# untitled.net
KiCad netlist of a schematic drawn in EAGLE
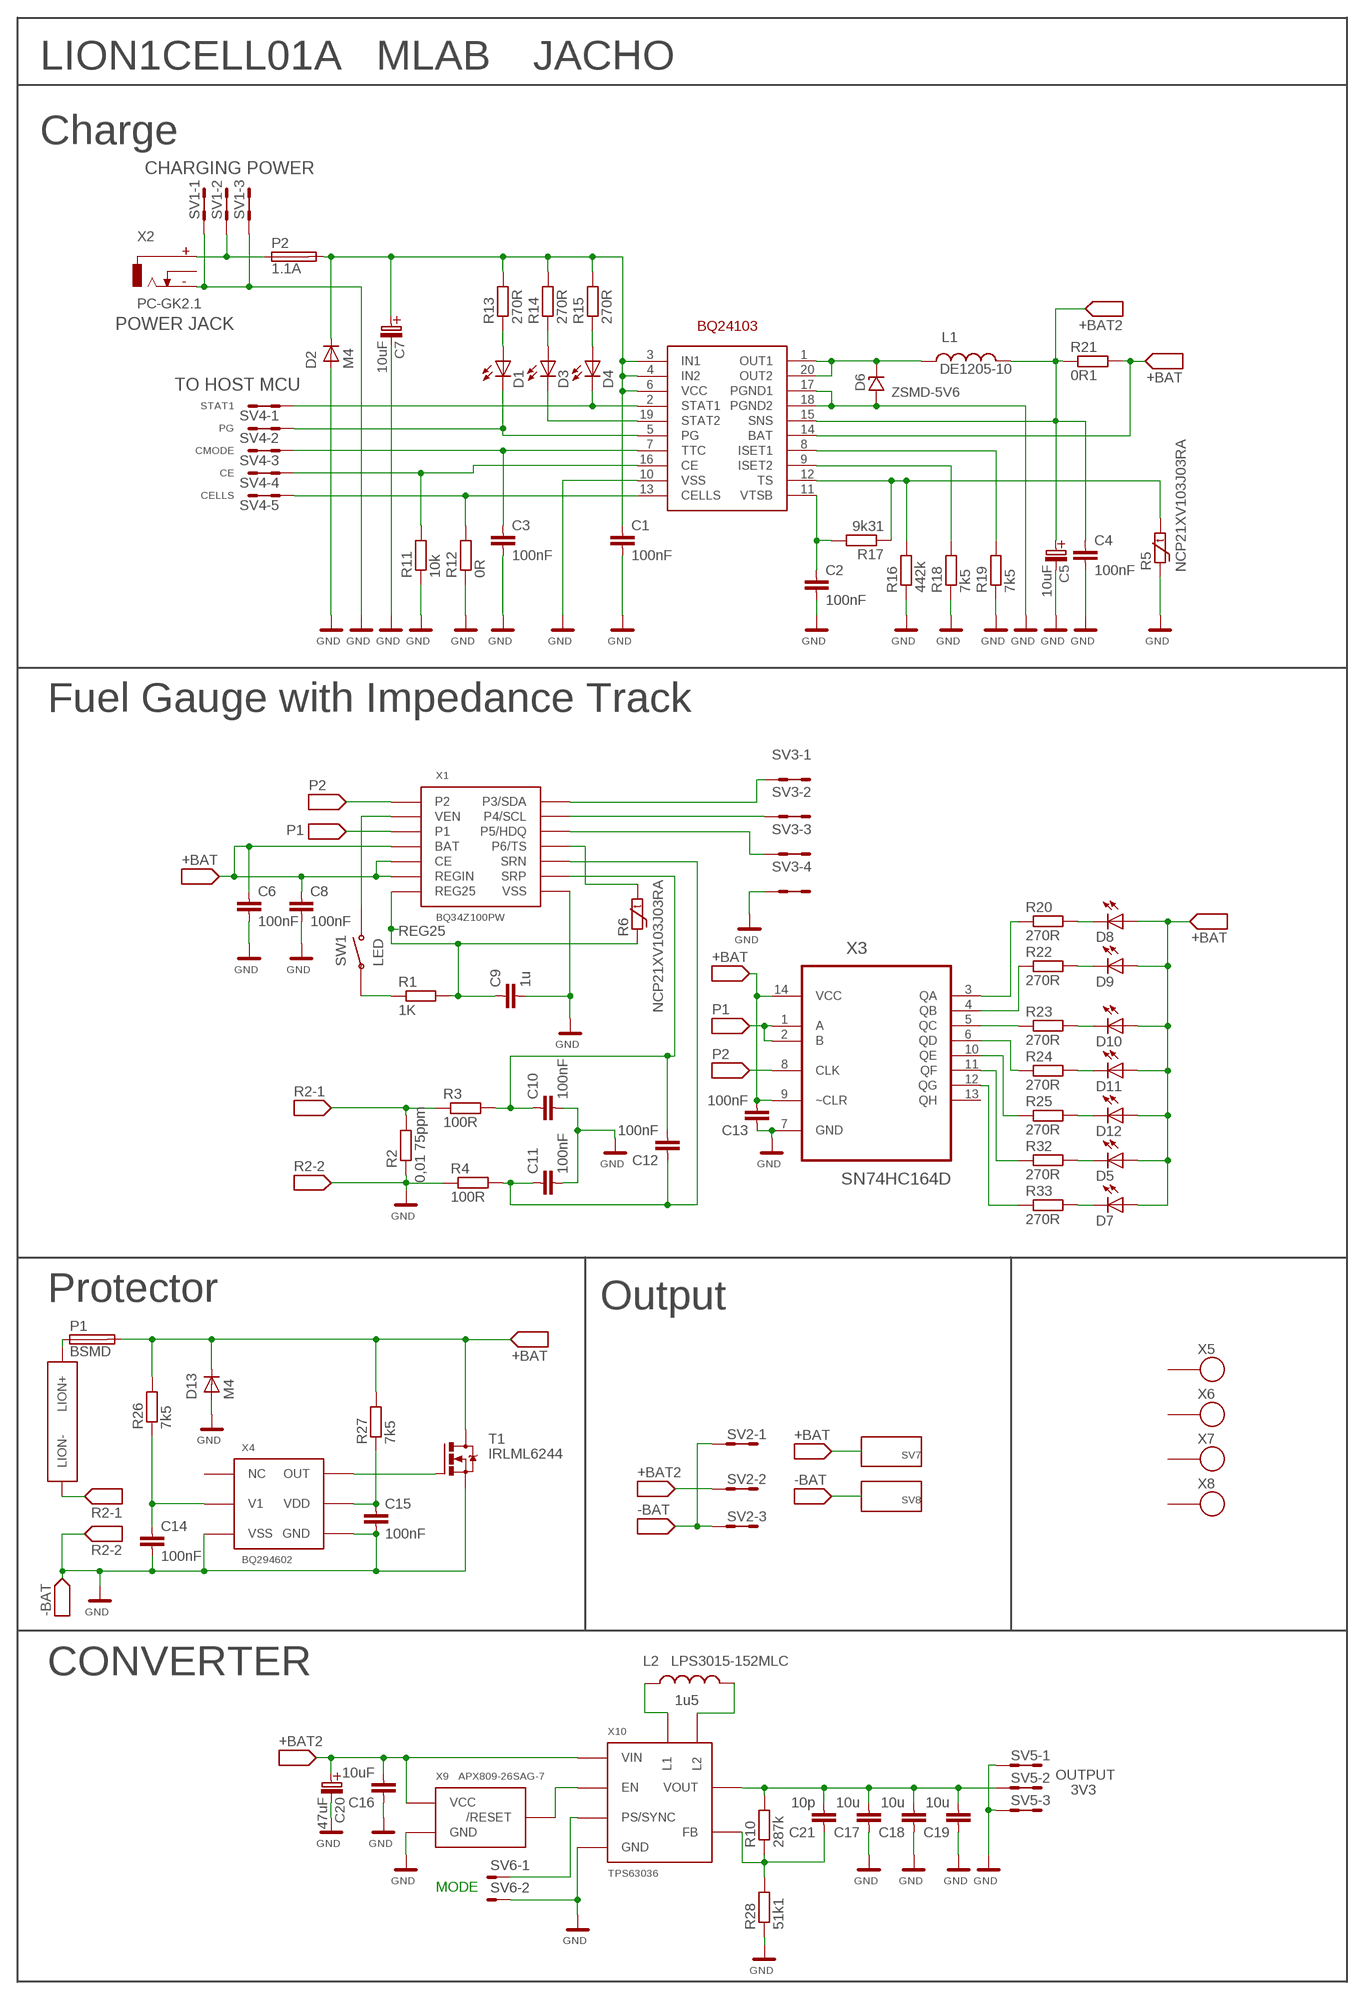
[diagram p0: schematic, sheet 1]

(export (version "E")
  (design (tool "Eeschema 10.0.6"))
  (components
    (comp (ref "C1")
      (value "100nF")
      (footprint "eagle-import:C0805")
      (libsource (lib "eagle-import") (part "C0805"))
    )
    (comp (ref "C2")
      (value "100nF")
      (footprint "eagle-import:C0805")
      (libsource (lib "eagle-import") (part "C0805"))
    )
    (comp (ref "C3")
      (value "100nF")
      (footprint "eagle-import:C0805")
      (libsource (lib "eagle-import") (part "C0805"))
    )
    (comp (ref "C4")
      (value "100nF")
      (footprint "eagle-import:C0805")
      (libsource (lib "eagle-import") (part "C0805"))
    )
    (comp (ref "C5") (value "10uF") (footprint "eagle-import:B") (libsource (lib "eagle-import") (part "B")))
    (comp (ref "C6")
      (value "100nF")
      (footprint "eagle-import:C0805")
      (libsource (lib "eagle-import") (part "C0805"))
    )
    (comp (ref "C7") (value "10uF") (footprint "eagle-import:B") (libsource (lib "eagle-import") (part "B")))
    (comp (ref "C8")
      (value "100nF")
      (footprint "eagle-import:C0805")
      (libsource (lib "eagle-import") (part "C0805"))
    )
    (comp (ref "C9")
      (value "1u")
      (footprint "eagle-import:C0805")
      (libsource (lib "eagle-import") (part "C0805"))
    )
    (comp (ref "C10")
      (value "100nF")
      (footprint "eagle-import:C0805")
      (libsource (lib "eagle-import") (part "C0805"))
    )
    (comp (ref "C11")
      (value "100nF")
      (footprint "eagle-import:C0805")
      (libsource (lib "eagle-import") (part "C0805"))
    )
    (comp (ref "C12")
      (value "100nF")
      (footprint "eagle-import:C0805")
      (libsource (lib "eagle-import") (part "C0805"))
    )
    (comp (ref "C13")
      (value "100nF")
      (footprint "eagle-import:C0805")
      (libsource (lib "eagle-import") (part "C0805"))
    )
    (comp (ref "C14")
      (value "100nF")
      (footprint "eagle-import:C0805")
      (libsource (lib "eagle-import") (part "C0805"))
    )
    (comp (ref "C15")
      (value "100nF")
      (footprint "eagle-import:C0805")
      (libsource (lib "eagle-import") (part "C0805"))
    )
    (comp (ref "C16")
      (value "10uF")
      (footprint "eagle-import:C0805")
      (libsource (lib "eagle-import") (part "C0805"))
    )
    (comp (ref "C17")
      (value "10u")
      (footprint "eagle-import:C0805")
      (libsource (lib "eagle-import") (part "C0805"))
    )
    (comp (ref "C18")
      (value "10u")
      (footprint "eagle-import:C0805")
      (libsource (lib "eagle-import") (part "C0805"))
    )
    (comp (ref "C19")
      (value "10u")
      (footprint "eagle-import:C0805")
      (libsource (lib "eagle-import") (part "C0805"))
    )
    (comp (ref "C20") (value "47uF") (footprint "eagle-import:B") (libsource (lib "eagle-import") (part "B")))
    (comp (ref "C21")
      (value "10p")
      (footprint "eagle-import:0603")
      (libsource (lib "eagle-import") (part "C0603"))
    )
    (comp (ref "D1")
      (value "LED1206_2")
      (footprint "eagle-import:1206_2")
      (libsource (lib "eagle-import") (part "LED1206_2"))
    )
    (comp (ref "D2")
      (value "M4")
      (footprint "eagle-import:SMB")
      (libsource (lib "eagle-import") (part "D-OB."))
    )
    (comp (ref "D3")
      (value "LED1206_2")
      (footprint "eagle-import:1206_2")
      (libsource (lib "eagle-import") (part "LED1206_2"))
    )
    (comp (ref "D4")
      (value "LED1206_2")
      (footprint "eagle-import:1206_2")
      (libsource (lib "eagle-import") (part "LED1206_2"))
    )
    (comp (ref "D5")
      (value "LED1206_2")
      (footprint "eagle-import:1206_2")
      (libsource (lib "eagle-import") (part "LED1206_2"))
    )
    (comp (ref "D6")
      (value "ZSMD-5V6")
      (footprint "eagle-import:MINIMELF")
      (libsource (lib "eagle-import") (part "D-ZENEROVA"))
    )
    (comp (ref "D7")
      (value "LED1206_2")
      (footprint "eagle-import:1206_2")
      (libsource (lib "eagle-import") (part "LED1206_2"))
    )
    (comp (ref "D8")
      (value "LED1206_2")
      (footprint "eagle-import:1206_2")
      (libsource (lib "eagle-import") (part "LED1206_2"))
    )
    (comp (ref "D9")
      (value "LED1206_2")
      (footprint "eagle-import:1206_2")
      (libsource (lib "eagle-import") (part "LED1206_2"))
    )
    (comp (ref "D10")
      (value "LED1206_2")
      (footprint "eagle-import:1206_2")
      (libsource (lib "eagle-import") (part "LED1206_2"))
    )
    (comp (ref "D11")
      (value "LED1206_2")
      (footprint "eagle-import:1206_2")
      (libsource (lib "eagle-import") (part "LED1206_2"))
    )
    (comp (ref "D12")
      (value "LED1206_2")
      (footprint "eagle-import:1206_2")
      (libsource (lib "eagle-import") (part "LED1206_2"))
    )
    (comp (ref "D13")
      (value "M4")
      (footprint "eagle-import:SMA")
      (libsource (lib "eagle-import") (part "D-OB.SMA"))
    )
    (comp (ref "L1")
      (value "DE1205-10")
      (footprint "eagle-import:DE1205-10")
      (libsource (lib "eagle-import") (part "DE1205-10"))
    )
    (comp (ref "L2")
      (value "LPS3015-152MLC")
      (footprint "eagle-import:LPS3015")
      (libsource (lib "eagle-import") (part "LPS3015"))
    )
    (comp (ref "P1")
      (value "BSMD")
      (footprint "eagle-import:2410")
      (libsource (lib "eagle-import") (part "POJISTKA2410"))
    )
    (comp (ref "P2")
      (value "1.1A")
      (footprint "eagle-import:1812")
      (libsource (lib "eagle-import") (part "POJISTKA_1812"))
    )
    (comp (ref "R1")
      (value "1K")
      (footprint "eagle-import:0805")
      (libsource (lib "eagle-import") (part "R0805"))
    )
    (comp (ref "R2")
      (value "0,01 75ppm")
      (footprint "eagle-import:0805")
      (libsource (lib "eagle-import") (part "R0805"))
    )
    (comp (ref "R3")
      (value "100R")
      (footprint "eagle-import:0805")
      (libsource (lib "eagle-import") (part "R0805"))
    )
    (comp (ref "R4")
      (value "100R")
      (footprint "eagle-import:0805")
      (libsource (lib "eagle-import") (part "R0805"))
    )
    (comp (ref "R5")
      (value "NCP21XV103J03RA")
      (footprint "eagle-import:0805")
      (libsource (lib "eagle-import") (part "TERMISTOR0805"))
    )
    (comp (ref "R6")
      (value "NCP21XV103J03RA")
      (footprint "eagle-import:0805")
      (libsource (lib "eagle-import") (part "TERMISTOR0805"))
    )
    (comp (ref "R10")
      (value "287k")
      (footprint "eagle-import:0603")
      (libsource (lib "eagle-import") (part "R0603"))
    )
    (comp (ref "R11")
      (value "10k")
      (footprint "eagle-import:0805")
      (libsource (lib "eagle-import") (part "R0805"))
    )
    (comp (ref "R12")
      (value "0R")
      (footprint "eagle-import:0805")
      (libsource (lib "eagle-import") (part "R0805"))
    )
    (comp (ref "R13")
      (value "270R")
      (footprint "eagle-import:0805")
      (libsource (lib "eagle-import") (part "R0805"))
    )
    (comp (ref "R14")
      (value "270R")
      (footprint "eagle-import:0805")
      (libsource (lib "eagle-import") (part "R0805"))
    )
    (comp (ref "R15")
      (value "270R")
      (footprint "eagle-import:0805")
      (libsource (lib "eagle-import") (part "R0805"))
    )
    (comp (ref "R16")
      (value "442k")
      (footprint "eagle-import:0805")
      (libsource (lib "eagle-import") (part "R0805"))
    )
    (comp (ref "R17")
      (value "9k31")
      (footprint "eagle-import:0805")
      (libsource (lib "eagle-import") (part "R0805"))
    )
    (comp (ref "R18")
      (value "7k5")
      (footprint "eagle-import:0805")
      (libsource (lib "eagle-import") (part "R0805"))
    )
    (comp (ref "R19")
      (value "7k5")
      (footprint "eagle-import:0805")
      (libsource (lib "eagle-import") (part "R0805"))
    )
    (comp (ref "R20")
      (value "270R")
      (footprint "eagle-import:0805")
      (libsource (lib "eagle-import") (part "R0805"))
    )
    (comp (ref "R21")
      (value "0R1")
      (footprint "eagle-import:R2512")
      (libsource (lib "eagle-import") (part "R-EU_R2512"))
    )
    (comp (ref "R22")
      (value "270R")
      (footprint "eagle-import:0805")
      (libsource (lib "eagle-import") (part "R0805"))
    )
    (comp (ref "R23")
      (value "270R")
      (footprint "eagle-import:0805")
      (libsource (lib "eagle-import") (part "R0805"))
    )
    (comp (ref "R24")
      (value "270R")
      (footprint "eagle-import:0805")
      (libsource (lib "eagle-import") (part "R0805"))
    )
    (comp (ref "R25")
      (value "270R")
      (footprint "eagle-import:0805")
      (libsource (lib "eagle-import") (part "R0805"))
    )
    (comp (ref "R26")
      (value "7k5")
      (footprint "eagle-import:0805")
      (libsource (lib "eagle-import") (part "R0805"))
    )
    (comp (ref "R27")
      (value "7k5")
      (footprint "eagle-import:0805")
      (libsource (lib "eagle-import") (part "R0805"))
    )
    (comp (ref "R28")
      (value "51k1")
      (footprint "eagle-import:0603")
      (libsource (lib "eagle-import") (part "R0603"))
    )
    (comp (ref "R32")
      (value "270R")
      (footprint "eagle-import:0805")
      (libsource (lib "eagle-import") (part "R0805"))
    )
    (comp (ref "R33")
      (value "270R")
      (footprint "eagle-import:0805")
      (libsource (lib "eagle-import") (part "R0805"))
    )
    (comp (ref "SV1")
      (value "MA03-2")
      (footprint "eagle-import:MA03-2")
      (libsource (lib "eagle-import") (part "MA03-2"))
    )
    (comp (ref "SV2")
      (value "MA03-2")
      (footprint "eagle-import:MA03-2")
      (libsource (lib "eagle-import") (part "MA03-2"))
    )
    (comp (ref "SV3")
      (value "MA04-2")
      (footprint "eagle-import:MA04-2")
      (libsource (lib "eagle-import") (part "MA04-2"))
    )
    (comp (ref "SV4")
      (value "MA05-2")
      (footprint "eagle-import:MA05-2")
      (libsource (lib "eagle-import") (part "MA05-2"))
    )
    (comp (ref "SV5")
      (value "MA03-2")
      (footprint "eagle-import:MA03-2")
      (libsource (lib "eagle-import") (part "MA03-2"))
    )
    (comp (ref "SV6")
      (value "MA02-1")
      (footprint "eagle-import:MA02-1")
      (libsource (lib "eagle-import") (part "MA02-1"))
    )
    (comp (ref "SV7")
      (value "WAGO256")
      (footprint "eagle-import:WAGO256")
      (libsource (lib "eagle-import") (part "WAGO256"))
    )
    (comp (ref "SV8")
      (value "WAGO256")
      (footprint "eagle-import:WAGO256")
      (libsource (lib "eagle-import") (part "WAGO256"))
    )
    (comp (ref "SW1")
      (value "TACT-64K")
      (footprint "eagle-import:TACT-64K")
      (libsource (lib "eagle-import") (part "TACT-64K"))
    )
    (comp (ref "T1")
      (value "IRLML6244")
      (footprint "eagle-import:SOT23")
      (libsource (lib "eagle-import") (part "IRLML6244TRPBF"))
    )
    (comp (ref "U$2")
      (value "LION1")
      (footprint "eagle-import:LION1")
      (libsource (lib "eagle-import") (part "LION1"))
    )
    (comp (ref "U1")
      (value "BQ24103")
      (footprint "eagle-import:RHL_R-VQFN-N20")
      (libsource (lib "eagle-import") (part "BQ24103"))
    )
    (comp (ref "X1")
      (value "BQ34Z100PW")
      (footprint "eagle-import:TSSOP14")
      (libsource (lib "eagle-import") (part "BQ34Z100PW"))
    )
    (comp (ref "X2")
      (value "DC2.1MM")
      (footprint "eagle-import:DC2.1MM")
      (libsource (lib "eagle-import") (part "DC2.1MM"))
    )
    (comp (ref "X3")
      (value "SN74HC164D")
      (footprint "eagle-import:SOIC127P600X175-14N")
      (libsource (lib "eagle-import") (part "SN74HC164D"))
    )
    (comp (ref "X4")
      (value "BQ294602")
      (footprint "eagle-import:SON_N6")
      (libsource (lib "eagle-import") (part "BQ294602"))
    )
    (comp (ref "X5")
      (value "SROUB3M")
      (footprint "eagle-import:SROUB3M")
      (libsource (lib "eagle-import") (part "SROUB3M"))
    )
    (comp (ref "X6")
      (value "SROUB3M")
      (footprint "eagle-import:SROUB3M")
      (libsource (lib "eagle-import") (part "SROUB3M"))
    )
    (comp (ref "X7")
      (value "SROUB3M")
      (footprint "eagle-import:SROUB3M")
      (libsource (lib "eagle-import") (part "SROUB3M"))
    )
    (comp (ref "X8")
      (value "SROUB3M")
      (footprint "eagle-import:SROUB3M")
      (libsource (lib "eagle-import") (part "SROUB3M"))
    )
    (comp (ref "X9")
      (value "APX809-26SAG-7")
      (footprint "eagle-import:SOT23")
      (libsource (lib "eagle-import") (part "APX809-26SA"))
    )
    (comp (ref "X10")
      (value "TPS63036")
      (footprint "eagle-import:DSBGA8")
      (libsource (lib "eagle-import") (part "TPS63036"))
    )
  )
  (nets
    (net (code "1") (name "/+BAT") (class "Default")
      (node (ref "C13") (pin "2") (pinfunction "2_2") (pintype "passive"))
      (node (ref "C6") (pin "1") (pinfunction "1_1") (pintype "passive"))
      (node (ref "C8") (pin "1") (pinfunction "1_1") (pintype "passive"))
      (node (ref "D10") (pin "A") (pinfunction "A_A") (pintype "passive"))
      (node (ref "D11") (pin "A") (pinfunction "A_A") (pintype "passive"))
      (node (ref "D12") (pin "A") (pinfunction "A_A") (pintype "passive"))
      (node (ref "D13") (pin "K") (pinfunction "C_K") (pintype "passive"))
      (node (ref "D5") (pin "A") (pinfunction "A_A") (pintype "passive"))
      (node (ref "D7") (pin "A") (pinfunction "A_A") (pintype "passive"))
      (node (ref "D8") (pin "A") (pinfunction "A_A") (pintype "passive"))
      (node (ref "D9") (pin "A") (pinfunction "A_A") (pintype "passive"))
      (node (ref "P1") (pin "2") (pinfunction "2_2") (pintype "passive"))
      (node (ref "R21") (pin "2") (pinfunction "2_2") (pintype "passive"))
      (node (ref "R26") (pin "2") (pinfunction "2_2") (pintype "passive"))
      (node (ref "R27") (pin "2") (pinfunction "2_2") (pintype "passive"))
      (node (ref "SV7") (pin "1") (pinfunction "P$1_1") (pintype "passive"))
      (node (ref "SV7") (pin "A1") (pinfunction "P$1_A1") (pintype "passive"))
      (node (ref "T1") (pin "3") (pinfunction "D_3") (pintype "passive"))
      (node (ref "U1") (pin "14") (pinfunction "BAT_14") (pintype "bidirectional"))
      (node (ref "X1") (pin "4") (pinfunction "BAT_4") (pintype "bidirectional"))
      (node (ref "X1") (pin "5") (pinfunction "CE_5") (pintype "bidirectional"))
      (node (ref "X1") (pin "6") (pinfunction "REGIN_6") (pintype "bidirectional"))
      (node (ref "X3") (pin "14") (pinfunction "VCC_14") (pintype "power_in"))
      (node (ref "X3") (pin "9") (pinfunction "~{CLR}_9") (pintype "input"))
    )
    (net (code "2") (name "/+BAT2") (class "Default")
      (node (ref "C16") (pin "2") (pinfunction "2_2") (pintype "passive"))
      (node (ref "C20") (pin "+") (pinfunction "C_EL+_+") (pintype "passive"))
      (node (ref "C4") (pin "1") (pinfunction "1_1") (pintype "passive"))
      (node (ref "C5") (pin "+") (pinfunction "C_EL+_+") (pintype "passive"))
      (node (ref "L1") (pin "P$2") (pinfunction "2_P$2") (pintype "passive"))
      (node (ref "R21") (pin "1") (pinfunction "1_1") (pintype "passive"))
      (node (ref "SV2") (pin "3") (pinfunction "K_3") (pintype "passive"))
      (node (ref "SV2") (pin "4") (pinfunction "K_4") (pintype "passive"))
      (node (ref "U1") (pin "15") (pinfunction "SNS_15") (pintype "bidirectional"))
      (node (ref "X10") (pin "A1") (pinfunction "VIN_A1") (pintype "input"))
      (node (ref "X9") (pin "3") (pinfunction "VCC_3") (pintype "input"))
    )
    (net (code "3") (name "/P1") (class "Default")
      (node (ref "X1") (pin "3") (pinfunction "P1_3") (pintype "bidirectional"))
      (node (ref "X3") (pin "1") (pinfunction "A_1") (pintype "input"))
      (node (ref "X3") (pin "2") (pinfunction "B_2") (pintype "input"))
    )
    (net (code "4") (name "/P2") (class "Default")
      (node (ref "X1") (pin "1") (pinfunction "P2_1") (pintype "bidirectional"))
      (node (ref "X3") (pin "8") (pinfunction "CLK_8") (pintype "input"))
    )
    (net (code "5") (name "/R2") (class "Default")
      (node (ref "R2") (pin "2") (pinfunction "2_2") (pintype "passive"))
      (node (ref "R3") (pin "1") (pinfunction "1_1") (pintype "passive"))
      (node (ref "U$2") (pin "-") (pinfunction "LION-_-") (pintype "bidirectional"))
      (node (ref "U$2") (pin "-1") (pinfunction "LION-_-1") (pintype "bidirectional"))
    )
    (net (code "6") (name "GND") (class "Default")
      (node (ref "C1") (pin "2") (pinfunction "2_2") (pintype "passive"))
      (node (ref "C10") (pin "2") (pinfunction "2_2") (pintype "passive"))
      (node (ref "C11") (pin "2") (pinfunction "2_2") (pintype "passive"))
      (node (ref "C13") (pin "1") (pinfunction "1_1") (pintype "passive"))
      (node (ref "C14") (pin "2") (pinfunction "2_2") (pintype "passive"))
      (node (ref "C15") (pin "2") (pinfunction "2_2") (pintype "passive"))
      (node (ref "C16") (pin "1") (pinfunction "1_1") (pintype "passive"))
      (node (ref "C17") (pin "1") (pinfunction "1_1") (pintype "passive"))
      (node (ref "C18") (pin "1") (pinfunction "1_1") (pintype "passive"))
      (node (ref "C19") (pin "1") (pinfunction "1_1") (pintype "passive"))
      (node (ref "C2") (pin "2") (pinfunction "2_2") (pintype "passive"))
      (node (ref "C20") (pin "-") (pinfunction "C_EL-_-") (pintype "passive"))
      (node (ref "C3") (pin "2") (pinfunction "2_2") (pintype "passive"))
      (node (ref "C4") (pin "2") (pinfunction "2_2") (pintype "passive"))
      (node (ref "C5") (pin "-") (pinfunction "C_EL-_-") (pintype "passive"))
      (node (ref "C6") (pin "2") (pinfunction "2_2") (pintype "passive"))
      (node (ref "C7") (pin "-") (pinfunction "C_EL-_-") (pintype "passive"))
      (node (ref "C8") (pin "2") (pinfunction "2_2") (pintype "passive"))
      (node (ref "C9") (pin "2") (pinfunction "2_2") (pintype "passive"))
      (node (ref "D13") (pin "A") (pinfunction "A_A") (pintype "passive"))
      (node (ref "D2") (pin "A") (pinfunction "A_A") (pintype "passive"))
      (node (ref "D6") (pin "A") (pinfunction "A_A") (pintype "passive"))
      (node (ref "R11") (pin "1") (pinfunction "1_1") (pintype "passive"))
      (node (ref "R12") (pin "1") (pinfunction "1_1") (pintype "passive"))
      (node (ref "R16") (pin "1") (pinfunction "1_1") (pintype "passive"))
      (node (ref "R18") (pin "1") (pinfunction "1_1") (pintype "passive"))
      (node (ref "R19") (pin "1") (pinfunction "1_1") (pintype "passive"))
      (node (ref "R2") (pin "1") (pinfunction "1_1") (pintype "passive"))
      (node (ref "R28") (pin "1") (pinfunction "1_1") (pintype "passive"))
      (node (ref "R4") (pin "1") (pinfunction "1_1") (pintype "passive"))
      (node (ref "R5") (pin "1") (pinfunction "1_1") (pintype "passive"))
      (node (ref "SV1") (pin "1") (pinfunction "K_1") (pintype "passive"))
      (node (ref "SV1") (pin "2") (pinfunction "K_2") (pintype "passive"))
      (node (ref "SV1") (pin "5") (pinfunction "K_5") (pintype "passive"))
      (node (ref "SV1") (pin "6") (pinfunction "K_6") (pintype "passive"))
      (node (ref "SV2") (pin "1") (pinfunction "K_1") (pintype "passive"))
      (node (ref "SV2") (pin "2") (pinfunction "K_2") (pintype "passive"))
      (node (ref "SV2") (pin "5") (pinfunction "K_5") (pintype "passive"))
      (node (ref "SV2") (pin "6") (pinfunction "K_6") (pintype "passive"))
      (node (ref "SV3") (pin "7") (pinfunction "K_7") (pintype "passive"))
      (node (ref "SV3") (pin "8") (pinfunction "K_8") (pintype "passive"))
      (node (ref "SV5") (pin "1") (pinfunction "K_1") (pintype "passive"))
      (node (ref "SV5") (pin "2") (pinfunction "K_2") (pintype "passive"))
      (node (ref "SV5") (pin "5") (pinfunction "K_5") (pintype "passive"))
      (node (ref "SV5") (pin "6") (pinfunction "K_6") (pintype "passive"))
      (node (ref "SV6") (pin "2") (pinfunction "P$1_2") (pintype "passive"))
      (node (ref "SV8") (pin "1") (pinfunction "P$1_1") (pintype "passive"))
      (node (ref "SV8") (pin "A1") (pinfunction "P$1_A1") (pintype "passive"))
      (node (ref "T1") (pin "2") (pinfunction "S_2") (pintype "passive"))
      (node (ref "U1") (pin "10") (pinfunction "VSS_10") (pintype "bidirectional"))
      (node (ref "U1") (pin "17") (pinfunction "PGND1_17") (pintype "bidirectional"))
      (node (ref "U1") (pin "18") (pinfunction "PGND2_18") (pintype "bidirectional"))
      (node (ref "X1") (pin "8") (pinfunction "VSS_8") (pintype "bidirectional"))
      (node (ref "X10") (pin "C2") (pinfunction "GND_C2") (pintype "passive"))
      (node (ref "X2") (pin "GND") (pinfunction "-_GND") (pintype "passive"))
      (node (ref "X3") (pin "7") (pinfunction "GND_7") (pintype "passive"))
      (node (ref "X4") (pin "3") (pinfunction "VSS_3") (pintype "bidirectional"))
      (node (ref "X4") (pin "4") (pinfunction "VSS_4") (pintype "bidirectional"))
      (node (ref "X4") (pin "7") (pinfunction "GND_7") (pintype "bidirectional"))
      (node (ref "X9") (pin "1") (pinfunction "GND_1") (pintype "passive"))
    )
    (net (code "7") (name "Net-(C7-C_EL+)") (class "Default")
      (node (ref "C1") (pin "1") (pinfunction "1_1") (pintype "passive"))
      (node (ref "C7") (pin "+") (pinfunction "C_EL+_+") (pintype "passive"))
      (node (ref "D2") (pin "K") (pinfunction "C_K") (pintype "passive"))
      (node (ref "P2") (pin "2") (pinfunction "2_2") (pintype "passive"))
      (node (ref "R13") (pin "2") (pinfunction "2_2") (pintype "passive"))
      (node (ref "R14") (pin "2") (pinfunction "2_2") (pintype "passive"))
      (node (ref "R15") (pin "2") (pinfunction "2_2") (pintype "passive"))
      (node (ref "U1") (pin "3") (pinfunction "IN1_3") (pintype "bidirectional"))
      (node (ref "U1") (pin "4") (pinfunction "IN2_4") (pintype "bidirectional"))
      (node (ref "U1") (pin "6") (pinfunction "VCC_6") (pintype "bidirectional"))
    )
    (net (code "8") (name "Net-(D1-C)") (class "Default")
      (node (ref "D1") (pin "K") (pinfunction "C_K") (pintype "passive"))
      (node (ref "SV4") (pin "3") (pinfunction "K_3") (pintype "passive"))
      (node (ref "SV4") (pin "4") (pinfunction "K_4") (pintype "passive"))
      (node (ref "U1") (pin "5") (pinfunction "PG_5") (pintype "bidirectional"))
    )
    (net (code "9") (name "Net-(D1-PadA)") (class "Default")
      (node (ref "D1") (pin "A") (pinfunction "A_A") (pintype "passive"))
      (node (ref "R13") (pin "1") (pinfunction "1_1") (pintype "passive"))
    )
    (net (code "10") (name "Net-(D3-C)") (class "Default")
      (node (ref "D3") (pin "K") (pinfunction "C_K") (pintype "passive"))
      (node (ref "U1") (pin "19") (pinfunction "STAT2_19") (pintype "bidirectional"))
    )
    (net (code "11") (name "Net-(D3-PadA)") (class "Default")
      (node (ref "D3") (pin "A") (pinfunction "A_A") (pintype "passive"))
      (node (ref "R14") (pin "1") (pinfunction "1_1") (pintype "passive"))
    )
    (net (code "12") (name "Net-(D4-C)") (class "Default")
      (node (ref "D4") (pin "K") (pinfunction "C_K") (pintype "passive"))
      (node (ref "SV4") (pin "1") (pinfunction "K_1") (pintype "passive"))
      (node (ref "SV4") (pin "2") (pinfunction "K_2") (pintype "passive"))
      (node (ref "U1") (pin "2") (pinfunction "STAT1_2") (pintype "bidirectional"))
    )
    (net (code "13") (name "Net-(D4-PadA)") (class "Default")
      (node (ref "D4") (pin "A") (pinfunction "A_A") (pintype "passive"))
      (node (ref "R15") (pin "1") (pinfunction "1_1") (pintype "passive"))
    )
    (net (code "14") (name "Net-(D5-C)") (class "Default")
      (node (ref "D5") (pin "K") (pinfunction "C_K") (pintype "passive"))
      (node (ref "R32") (pin "2") (pinfunction "2_2") (pintype "passive"))
    )
    (net (code "15") (name "Net-(D6-K)") (class "Default")
      (node (ref "D6") (pin "C") (pinfunction "K_C") (pintype "passive"))
      (node (ref "L1") (pin "P$1") (pinfunction "1_P$1") (pintype "passive"))
      (node (ref "U1") (pin "1") (pinfunction "OUT1_1") (pintype "bidirectional"))
      (node (ref "U1") (pin "20") (pinfunction "OUT2_20") (pintype "bidirectional"))
    )
    (net (code "16") (name "Net-(D7-C)") (class "Default")
      (node (ref "D7") (pin "K") (pinfunction "C_K") (pintype "passive"))
      (node (ref "R33") (pin "2") (pinfunction "2_2") (pintype "passive"))
    )
    (net (code "17") (name "Net-(D8-C)") (class "Default")
      (node (ref "D8") (pin "K") (pinfunction "C_K") (pintype "passive"))
      (node (ref "R20") (pin "2") (pinfunction "2_2") (pintype "passive"))
    )
    (net (code "18") (name "Net-(D9-C)") (class "Default")
      (node (ref "D9") (pin "K") (pinfunction "C_K") (pintype "passive"))
      (node (ref "R22") (pin "2") (pinfunction "2_2") (pintype "passive"))
    )
    (net (code "19") (name "Net-(D10-C)") (class "Default")
      (node (ref "D10") (pin "K") (pinfunction "C_K") (pintype "passive"))
      (node (ref "R23") (pin "2") (pinfunction "2_2") (pintype "passive"))
    )
    (net (code "20") (name "Net-(D11-C)") (class "Default")
      (node (ref "D11") (pin "K") (pinfunction "C_K") (pintype "passive"))
      (node (ref "R24") (pin "2") (pinfunction "2_2") (pintype "passive"))
    )
    (net (code "21") (name "Net-(D12-C)") (class "Default")
      (node (ref "D12") (pin "K") (pinfunction "C_K") (pintype "passive"))
      (node (ref "R25") (pin "2") (pinfunction "2_2") (pintype "passive"))
    )
    (net (code "22") (name "Net-(P1-Pad1)") (class "Default")
      (node (ref "P1") (pin "1") (pinfunction "1_1") (pintype "passive"))
      (node (ref "U$2") (pin "+") (pinfunction "LION+_+") (pintype "bidirectional"))
      (node (ref "U$2") (pin "+1") (pinfunction "LION+_+1") (pintype "bidirectional"))
    )
    (net (code "23") (name "Net-(P2-Pad1)") (class "Default")
      (node (ref "P2") (pin "1") (pinfunction "1_1") (pintype "passive"))
      (node (ref "SV1") (pin "3") (pinfunction "K_3") (pintype "passive"))
      (node (ref "SV1") (pin "4") (pinfunction "K_4") (pintype "passive"))
      (node (ref "X2") (pin "+") (pinfunction "+_+") (pintype "passive"))
    )
    (net (code "24") (name "Net-(R1-Pad1)") (class "Default")
      (node (ref "R1") (pin "1") (pinfunction "1_1") (pintype "passive"))
      (node (ref "SW1") (pin "P$1") (pinfunction "P$1_P$1") (pintype "passive"))
      (node (ref "SW1") (pin "P$2") (pinfunction "P$1_P$2") (pintype "passive"))
    )
    (net (code "25") (name "Net-(SV6A-P$1)") (class "Default")
      (node (ref "SV6") (pin "1") (pinfunction "P$1_1") (pintype "passive"))
      (node (ref "X10") (pin "B2") (pinfunction "PS/SYNC_B2") (pintype "input"))
    )
    (net (code "26") (name "Net-(T1-G)") (class "Default")
      (node (ref "T1") (pin "1") (pinfunction "G_1") (pintype "passive"))
      (node (ref "X4") (pin "6") (pinfunction "OUT_6") (pintype "bidirectional"))
    )
    (net (code "27") (name "Net-(U1-CE)") (class "Default")
      (node (ref "R11") (pin "2") (pinfunction "2_2") (pintype "passive"))
      (node (ref "SV4") (pin "7") (pinfunction "K_7") (pintype "passive"))
      (node (ref "SV4") (pin "8") (pinfunction "K_8") (pintype "passive"))
      (node (ref "U1") (pin "16") (pinfunction "CE_16") (pintype "bidirectional"))
    )
    (net (code "28") (name "Net-(U1-CELLS)") (class "Default")
      (node (ref "R12") (pin "2") (pinfunction "2_2") (pintype "passive"))
      (node (ref "SV4") (pin "10") (pinfunction "K_10") (pintype "passive"))
      (node (ref "SV4") (pin "9") (pinfunction "K_9") (pintype "passive"))
      (node (ref "U1") (pin "13") (pinfunction "CELLS_13") (pintype "bidirectional"))
    )
    (net (code "29") (name "Net-(U1-ISET1)") (class "Default")
      (node (ref "R19") (pin "2") (pinfunction "2_2") (pintype "passive"))
      (node (ref "U1") (pin "8") (pinfunction "ISET1_8") (pintype "bidirectional"))
    )
    (net (code "30") (name "Net-(U1-ISET2)") (class "Default")
      (node (ref "R18") (pin "2") (pinfunction "2_2") (pintype "passive"))
      (node (ref "U1") (pin "9") (pinfunction "ISET2_9") (pintype "bidirectional"))
    )
    (net (code "31") (name "Net-(U1-TS)") (class "Default")
      (node (ref "R16") (pin "2") (pinfunction "2_2") (pintype "passive"))
      (node (ref "R17") (pin "1") (pinfunction "1_1") (pintype "passive"))
      (node (ref "R5") (pin "2") (pinfunction "2_2") (pintype "passive"))
      (node (ref "U1") (pin "12") (pinfunction "TS_12") (pintype "bidirectional"))
    )
    (net (code "32") (name "Net-(U1-TTC)") (class "Default")
      (node (ref "C3") (pin "1") (pinfunction "1_1") (pintype "passive"))
      (node (ref "SV4") (pin "5") (pinfunction "K_5") (pintype "passive"))
      (node (ref "SV4") (pin "6") (pinfunction "K_6") (pintype "passive"))
      (node (ref "U1") (pin "7") (pinfunction "TTC_7") (pintype "bidirectional"))
    )
    (net (code "33") (name "Net-(U1-VTSB)") (class "Default")
      (node (ref "C2") (pin "1") (pinfunction "1_1") (pintype "passive"))
      (node (ref "R17") (pin "2") (pinfunction "2_2") (pintype "passive"))
      (node (ref "U1") (pin "11") (pinfunction "VTSB_11") (pintype "bidirectional"))
    )
    (net (code "34") (name "Net-(X1-P3{slash}SDA)") (class "Default")
      (node (ref "SV3") (pin "1") (pinfunction "K_1") (pintype "passive"))
      (node (ref "SV3") (pin "2") (pinfunction "K_2") (pintype "passive"))
      (node (ref "X1") (pin "14") (pinfunction "P3/SDA_14") (pintype "bidirectional"))
    )
    (net (code "35") (name "Net-(X1-P4{slash}SCL)") (class "Default")
      (node (ref "SV3") (pin "3") (pinfunction "K_3") (pintype "passive"))
      (node (ref "SV3") (pin "4") (pinfunction "K_4") (pintype "passive"))
      (node (ref "X1") (pin "13") (pinfunction "P4/SCL_13") (pintype "bidirectional"))
    )
    (net (code "36") (name "Net-(X1-P5{slash}HDQ)") (class "Default")
      (node (ref "SV3") (pin "5") (pinfunction "K_5") (pintype "passive"))
      (node (ref "SV3") (pin "6") (pinfunction "K_6") (pintype "passive"))
      (node (ref "X1") (pin "12") (pinfunction "P5/HDQ_12") (pintype "bidirectional"))
    )
    (net (code "37") (name "Net-(X1-P6{slash}TS)") (class "Default")
      (node (ref "R6") (pin "2") (pinfunction "2_2") (pintype "passive"))
      (node (ref "X1") (pin "11") (pinfunction "P6/TS_11") (pintype "bidirectional"))
    )
    (net (code "38") (name "Net-(X1-REG25)") (class "Default")
      (node (ref "C9") (pin "1") (pinfunction "1_1") (pintype "passive"))
      (node (ref "R1") (pin "2") (pinfunction "2_2") (pintype "passive"))
      (node (ref "R6") (pin "1") (pinfunction "1_1") (pintype "passive"))
      (node (ref "X1") (pin "7") (pinfunction "REG25_7") (pintype "bidirectional"))
    )
    (net (code "39") (name "Net-(X1-SRN)") (class "Default")
      (node (ref "C11") (pin "1") (pinfunction "1_1") (pintype "passive"))
      (node (ref "C12") (pin "1") (pinfunction "1_1") (pintype "passive"))
      (node (ref "R4") (pin "2") (pinfunction "2_2") (pintype "passive"))
      (node (ref "X1") (pin "10") (pinfunction "SRN_10") (pintype "bidirectional"))
    )
    (net (code "40") (name "Net-(X1-SRP)") (class "Default")
      (node (ref "C10") (pin "1") (pinfunction "1_1") (pintype "passive"))
      (node (ref "C12") (pin "2") (pinfunction "2_2") (pintype "passive"))
      (node (ref "R3") (pin "2") (pinfunction "2_2") (pintype "passive"))
      (node (ref "X1") (pin "9") (pinfunction "SRP_9") (pintype "bidirectional"))
    )
    (net (code "41") (name "Net-(X1-VEN)") (class "Default")
      (node (ref "SW1") (pin "P$3") (pinfunction "P$2_P$3") (pintype "passive"))
      (node (ref "SW1") (pin "P$4") (pinfunction "P$2_P$4") (pintype "passive"))
      (node (ref "X1") (pin "2") (pinfunction "VEN_2") (pintype "bidirectional"))
    )
    (net (code "42") (name "Net-(X3-QA)") (class "Default")
      (node (ref "R20") (pin "1") (pinfunction "1_1") (pintype "passive"))
      (node (ref "X3") (pin "3") (pinfunction "QA_3") (pintype "output"))
    )
    (net (code "43") (name "Net-(X3-QB)") (class "Default")
      (node (ref "R22") (pin "1") (pinfunction "1_1") (pintype "passive"))
      (node (ref "X3") (pin "4") (pinfunction "QB_4") (pintype "output"))
    )
    (net (code "44") (name "Net-(X3-QC)") (class "Default")
      (node (ref "R23") (pin "1") (pinfunction "1_1") (pintype "passive"))
      (node (ref "X3") (pin "5") (pinfunction "QC_5") (pintype "output"))
    )
    (net (code "45") (name "Net-(X3-QD)") (class "Default")
      (node (ref "R24") (pin "1") (pinfunction "1_1") (pintype "passive"))
      (node (ref "X3") (pin "6") (pinfunction "QD_6") (pintype "output"))
    )
    (net (code "46") (name "Net-(X3-QE)") (class "Default")
      (node (ref "R25") (pin "1") (pinfunction "1_1") (pintype "passive"))
      (node (ref "X3") (pin "10") (pinfunction "QE_10") (pintype "output"))
    )
    (net (code "47") (name "Net-(X3-QF)") (class "Default")
      (node (ref "R32") (pin "1") (pinfunction "1_1") (pintype "passive"))
      (node (ref "X3") (pin "11") (pinfunction "QF_11") (pintype "output"))
    )
    (net (code "48") (name "Net-(X3-QG)") (class "Default")
      (node (ref "R33") (pin "1") (pinfunction "1_1") (pintype "passive"))
      (node (ref "X3") (pin "12") (pinfunction "QG_12") (pintype "output"))
    )
    (net (code "49") (name "Net-(X4-V1)") (class "Default")
      (node (ref "C14") (pin "1") (pinfunction "1_1") (pintype "passive"))
      (node (ref "R26") (pin "1") (pinfunction "1_1") (pintype "passive"))
      (node (ref "X4") (pin "2") (pinfunction "V1_2") (pintype "bidirectional"))
    )
    (net (code "50") (name "Net-(X4-VDD)") (class "Default")
      (node (ref "C15") (pin "1") (pinfunction "1_1") (pintype "passive"))
      (node (ref "R27") (pin "1") (pinfunction "1_1") (pintype "passive"))
      (node (ref "X4") (pin "5") (pinfunction "VDD_5") (pintype "bidirectional"))
    )
    (net (code "51") (name "Net-(X10-EN)") (class "Default")
      (node (ref "X10") (pin "A2") (pinfunction "EN_A2") (pintype "input"))
      (node (ref "X9") (pin "2") (pinfunction "/RESET_2") (pintype "passive"))
    )
    (net (code "52") (name "Net-(X10-FB)") (class "Default")
      (node (ref "C21") (pin "1") (pinfunction "1_1") (pintype "passive"))
      (node (ref "R10") (pin "1") (pinfunction "1_1") (pintype "passive"))
      (node (ref "R28") (pin "2") (pinfunction "2_2") (pintype "passive"))
      (node (ref "X10") (pin "D2") (pinfunction "FB_D2") (pintype "input"))
    )
    (net (code "53") (name "Net-(X10-L1)") (class "Default")
      (node (ref "L2") (pin "1-1") (pinfunction "1_1-1") (pintype "passive"))
      (node (ref "L2") (pin "1-2") (pinfunction "1_1-2") (pintype "passive"))
      (node (ref "L2") (pin "1-3") (pinfunction "1_1-3") (pintype "passive"))
      (node (ref "X10") (pin "B1") (pinfunction "L1_B1") (pintype "passive"))
    )
    (net (code "54") (name "Net-(X10-L2)") (class "Default")
      (node (ref "L2") (pin "2-1") (pinfunction "2_2-1") (pintype "passive"))
      (node (ref "L2") (pin "2-2") (pinfunction "2_2-2") (pintype "passive"))
      (node (ref "L2") (pin "2-3") (pinfunction "2_2-3") (pintype "passive"))
      (node (ref "X10") (pin "C1") (pinfunction "L2_C1") (pintype "passive"))
    )
    (net (code "55") (name "Net-(X10-VOUT)") (class "Default")
      (node (ref "C17") (pin "2") (pinfunction "2_2") (pintype "passive"))
      (node (ref "C18") (pin "2") (pinfunction "2_2") (pintype "passive"))
      (node (ref "C19") (pin "2") (pinfunction "2_2") (pintype "passive"))
      (node (ref "C21") (pin "2") (pinfunction "2_2") (pintype "passive"))
      (node (ref "R10") (pin "2") (pinfunction "2_2") (pintype "passive"))
      (node (ref "SV5") (pin "3") (pinfunction "K_3") (pintype "passive"))
      (node (ref "SV5") (pin "4") (pinfunction "K_4") (pintype "passive"))
      (node (ref "X10") (pin "D1") (pinfunction "VOUT_D1") (pintype "output"))
    )
    (net (code "56") (name "unconnected-(X2-PadSW)") (class "Default")
      (node (ref "X2") (pin "SW") (pinfunction "SW_SW") (pintype "passive"))
    )
    (net (code "57") (name "unconnected-(X3-QH-Pad13)") (class "Default")
      (node (ref "X3") (pin "13") (pinfunction "QH_13") (pintype "output"))
    )
    (net (code "58") (name "unconnected-(X4-NC-Pad1)") (class "Default")
      (node (ref "X4") (pin "1") (pinfunction "NC_1") (pintype "bidirectional"))
    )
    (net (code "59") (name "unconnected-(X5-PadP$1)") (class "Default")
      (node (ref "X5") (pin "P$1") (pinfunction "P$1_P$1") (pintype "bidirectional"))
    )
    (net (code "60") (name "unconnected-(X6-PadP$1)") (class "Default")
      (node (ref "X6") (pin "P$1") (pinfunction "P$1_P$1") (pintype "bidirectional"))
    )
    (net (code "61") (name "unconnected-(X7-PadP$1)") (class "Default")
      (node (ref "X7") (pin "P$1") (pinfunction "P$1_P$1") (pintype "bidirectional"))
    )
    (net (code "62") (name "unconnected-(X8-PadP$1)") (class "Default")
      (node (ref "X8") (pin "P$1") (pinfunction "P$1_P$1") (pintype "bidirectional"))
    )
  )
)
